# Cell_121_sheet_2.net
KiCad netlist of a schematic drawn in Altium Designer
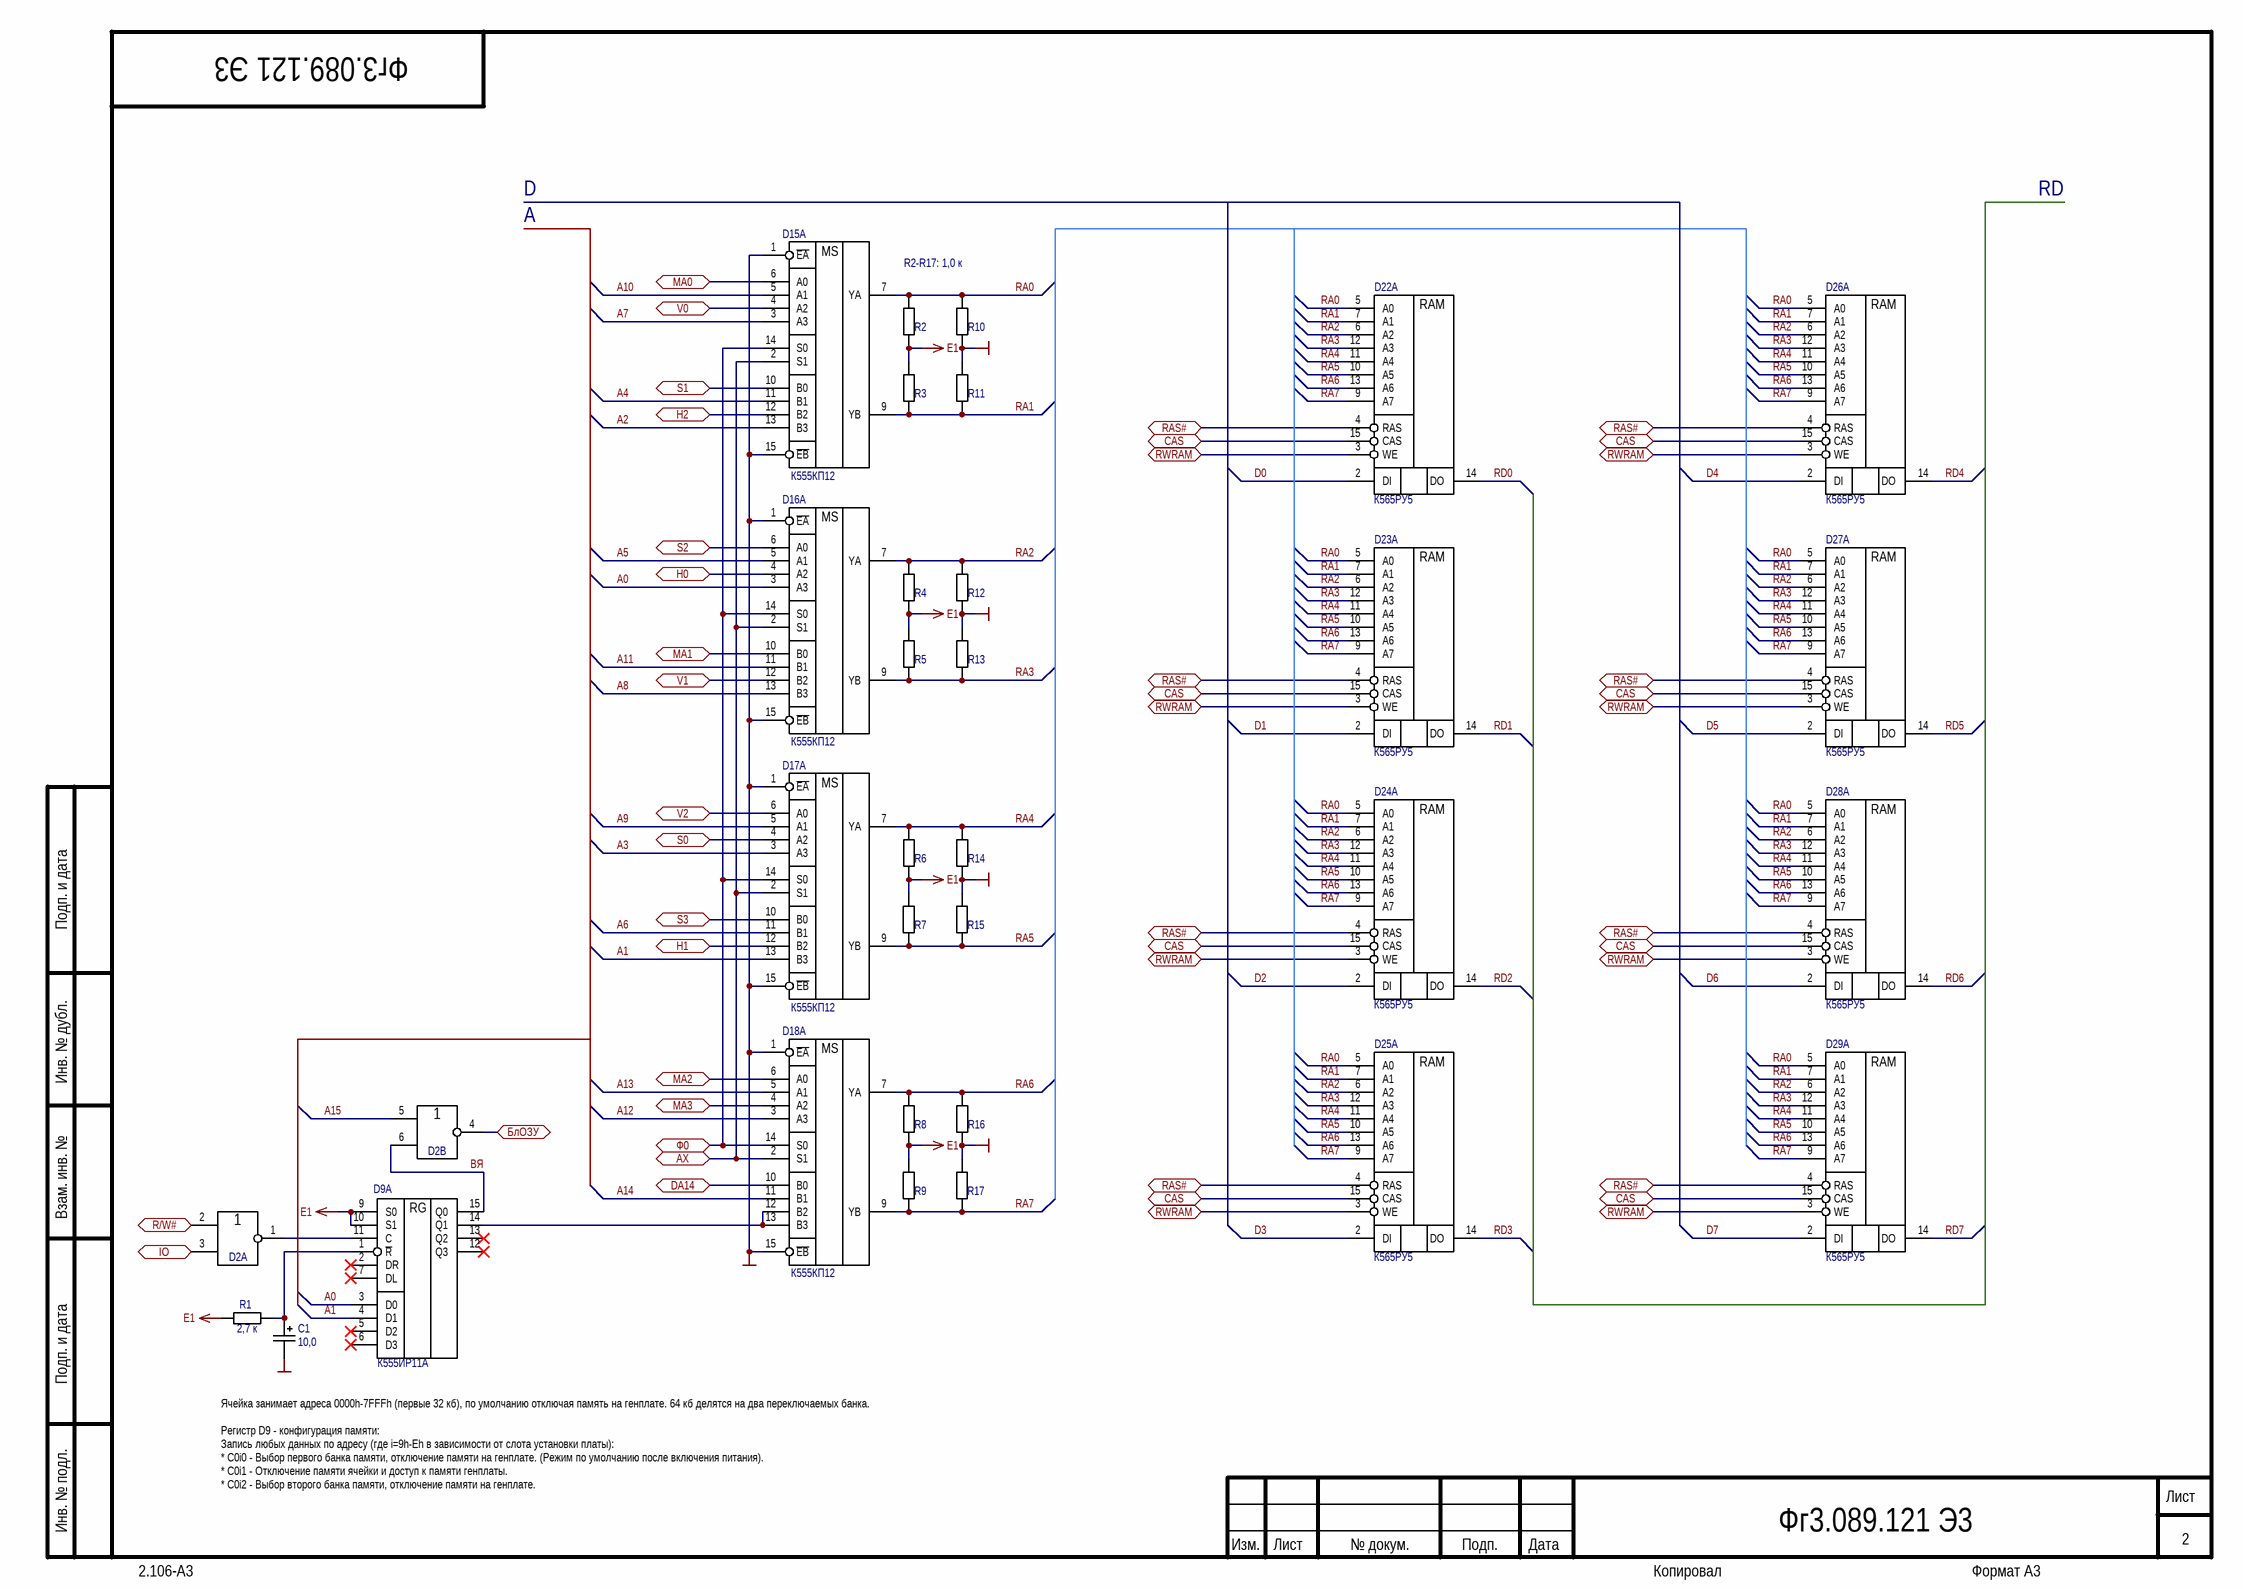
[diagram p0: Cell_121_sheet_2.SchDoc]

(export (version "E")
  (design (tool "Eeschema 10.0.6"))
  (components
    (comp (ref "C1")
      (value "10,0")
      (footprint "CP25")
      (description "К53-14")
      (libsource (lib "Agat") (part "К53-14"))
    )
    (comp (ref "D2")
      (value "К555ЛЕ1")
      (footprint "201.14")
      (fields (field (name "MANUFACTURERPARTNUMBER") "К555ЛА3"))
      (libsource (lib "Agat") (part "К555ЛЕ1"))
    )
    (comp (ref "D9")
      (value "К555ИР11А")
      (footprint "201.16")
      (fields (field (name "MANUFACTURERPARTNUMBER") "КР531ИЕ17"))
      (libsource (lib "Agat") (part "К555ИР11А"))
    )
    (comp (ref "D15")
      (value "К555КП12")
      (footprint "201.16")
      (fields (field (name "MANUFACTURERPARTNUMBER") "К155КП2"))
      (libsource (lib "Agat") (part "К555КП12"))
    )
    (comp (ref "D16")
      (value "К555КП12")
      (footprint "201.16")
      (fields (field (name "MANUFACTURERPARTNUMBER") "К155КП2"))
      (libsource (lib "Agat") (part "К555КП12"))
    )
    (comp (ref "D17")
      (value "К555КП12")
      (footprint "201.16")
      (fields (field (name "MANUFACTURERPARTNUMBER") "К155КП2"))
      (libsource (lib "Agat") (part "К555КП12"))
    )
    (comp (ref "D18")
      (value "К555КП12")
      (footprint "201.16")
      (fields (field (name "MANUFACTURERPARTNUMBER") "К155КП2"))
      (libsource (lib "Agat") (part "К555КП12"))
    )
    (comp (ref "D22") (value "К565РУ5") (footprint "201.16") (libsource (lib "Agat") (part "К565РУ5")))
    (comp (ref "D23") (value "К565РУ5") (footprint "201.16") (libsource (lib "Agat") (part "К565РУ5")))
    (comp (ref "D24") (value "К565РУ5") (footprint "201.16") (libsource (lib "Agat") (part "К565РУ5")))
    (comp (ref "D25") (value "К565РУ5") (footprint "201.16") (libsource (lib "Agat") (part "К565РУ5")))
    (comp (ref "D26") (value "К565РУ5") (footprint "201.16") (libsource (lib "Agat") (part "К565РУ5")))
    (comp (ref "D27") (value "К565РУ5") (footprint "201.16") (libsource (lib "Agat") (part "К565РУ5")))
    (comp (ref "D28") (value "К565РУ5") (footprint "201.16") (libsource (lib "Agat") (part "К565РУ5")))
    (comp (ref "D29") (value "К565РУ5") (footprint "201.16") (libsource (lib "Agat") (part "К565РУ5")))
    (comp (ref "R1")
      (value "2,7 к")
      (footprint "R10")
      (description "Резистор")
      (libsource (lib "") (part "С2-23_2"))
    )
    (comp (ref "R2")
      (value "1 к")
      (footprint "R10")
      (description "Резистор")
      (libsource (lib "Agat") (part "С2-23"))
    )
    (comp (ref "R3")
      (value "1 к")
      (footprint "R10")
      (description "Резистор")
      (libsource (lib "Agat") (part "С2-23"))
    )
    (comp (ref "R4")
      (value "1 к")
      (footprint "R10")
      (description "Резистор")
      (libsource (lib "Agat") (part "С2-23"))
    )
    (comp (ref "R5")
      (value "1 к")
      (footprint "R10")
      (description "Резистор")
      (libsource (lib "Agat") (part "С2-23"))
    )
    (comp (ref "R6")
      (value "1 к")
      (footprint "R10")
      (description "Резистор")
      (libsource (lib "Agat") (part "С2-23"))
    )
    (comp (ref "R7")
      (value "1 к")
      (footprint "R10")
      (description "Резистор")
      (libsource (lib "") (part "С2-23_1"))
    )
    (comp (ref "R8")
      (value "1 к")
      (footprint "R10")
      (description "Резистор")
      (libsource (lib "Agat") (part "С2-23"))
    )
    (comp (ref "R9")
      (value "1 к")
      (footprint "R10")
      (description "Резистор")
      (libsource (lib "") (part "С2-23_1"))
    )
    (comp (ref "R10")
      (value "1 к")
      (footprint "R10")
      (description "Резистор")
      (libsource (lib "Agat") (part "С2-23"))
    )
    (comp (ref "R11")
      (value "1 к")
      (footprint "R10")
      (description "Резистор")
      (libsource (lib "Agat") (part "С2-23"))
    )
    (comp (ref "R12")
      (value "1 к")
      (footprint "R10")
      (description "Резистор")
      (libsource (lib "Agat") (part "С2-23"))
    )
    (comp (ref "R13")
      (value "1 к")
      (footprint "R10")
      (description "Резистор")
      (libsource (lib "Agat") (part "С2-23"))
    )
    (comp (ref "R14")
      (value "1 к")
      (footprint "R10")
      (description "Резистор")
      (libsource (lib "Agat") (part "С2-23"))
    )
    (comp (ref "R15")
      (value "1 к")
      (footprint "R10")
      (description "Резистор")
      (libsource (lib "") (part "С2-23_1"))
    )
    (comp (ref "R16")
      (value "1 к")
      (footprint "R10")
      (description "Резистор")
      (libsource (lib "Agat") (part "С2-23"))
    )
    (comp (ref "R17")
      (value "1 к")
      (footprint "R10")
      (description "Резистор")
      (libsource (lib "") (part "С2-23_1"))
    )
  )
  (nets
    (net (code "1") (name "/A0") (class "Default")
      (node (ref "D16") (pin "3") (pinfunction "A3_3") (pintype "passive"))
      (node (ref "D9") (pin "3") (pinfunction "D0_3") (pintype "passive"))
    )
    (net (code "2") (name "/A1") (class "Default")
      (node (ref "D17") (pin "13") (pinfunction "B3_13") (pintype "passive"))
      (node (ref "D9") (pin "4") (pinfunction "D1_4") (pintype "passive"))
    )
    (net (code "3") (name "/A2") (class "Default")
      (node (ref "D15") (pin "13") (pinfunction "B3_13") (pintype "passive"))
    )
    (net (code "4") (name "/A3") (class "Default")
      (node (ref "D17") (pin "3") (pinfunction "A3_3") (pintype "passive"))
    )
    (net (code "5") (name "/A4") (class "Default")
      (node (ref "D15") (pin "11") (pinfunction "B1_11") (pintype "passive"))
    )
    (net (code "6") (name "/A5") (class "Default")
      (node (ref "D16") (pin "5") (pinfunction "A1_5") (pintype "passive"))
    )
    (net (code "7") (name "/A6") (class "Default")
      (node (ref "D17") (pin "11") (pinfunction "B1_11") (pintype "passive"))
    )
    (net (code "8") (name "/A7") (class "Default")
      (node (ref "D15") (pin "3") (pinfunction "A3_3") (pintype "passive"))
    )
    (net (code "9") (name "/A8") (class "Default")
      (node (ref "D16") (pin "13") (pinfunction "B3_13") (pintype "passive"))
    )
    (net (code "10") (name "/A9") (class "Default")
      (node (ref "D17") (pin "5") (pinfunction "A1_5") (pintype "passive"))
    )
    (net (code "11") (name "/A10") (class "Default")
      (node (ref "D15") (pin "5") (pinfunction "A1_5") (pintype "passive"))
    )
    (net (code "12") (name "/A11") (class "Default")
      (node (ref "D16") (pin "11") (pinfunction "B1_11") (pintype "passive"))
    )
    (net (code "13") (name "/A12") (class "Default")
      (node (ref "D18") (pin "3") (pinfunction "A3_3") (pintype "passive"))
    )
    (net (code "14") (name "/A13") (class "Default")
      (node (ref "D18") (pin "5") (pinfunction "A1_5") (pintype "passive"))
    )
    (net (code "15") (name "/A14") (class "Default")
      (node (ref "D18") (pin "11") (pinfunction "B1_11") (pintype "passive"))
    )
    (net (code "16") (name "/A15") (class "Default")
      (node (ref "D2") (pin "5") (pinfunction "A_5") (pintype "passive"))
    )
    (net (code "17") (name "/AX") (class "Default")
      (node (ref "D15") (pin "2") (pinfunction "S1_2") (pintype "passive"))
      (node (ref "D16") (pin "2") (pinfunction "S1_2") (pintype "passive"))
      (node (ref "D17") (pin "2") (pinfunction "S1_2") (pintype "passive"))
      (node (ref "D18") (pin "2") (pinfunction "S1_2") (pintype "passive"))
    )
    (net (code "18") (name "/CAS") (class "Default")
      (node (ref "D22") (pin "15") (pinfunction "CAS_15") (pintype "passive"))
      (node (ref "D23") (pin "15") (pinfunction "CAS_15") (pintype "passive"))
      (node (ref "D24") (pin "15") (pinfunction "CAS_15") (pintype "passive"))
      (node (ref "D25") (pin "15") (pinfunction "CAS_15") (pintype "passive"))
      (node (ref "D26") (pin "15") (pinfunction "CAS_15") (pintype "passive"))
      (node (ref "D27") (pin "15") (pinfunction "CAS_15") (pintype "passive"))
      (node (ref "D28") (pin "15") (pinfunction "CAS_15") (pintype "passive"))
      (node (ref "D29") (pin "15") (pinfunction "CAS_15") (pintype "passive"))
    )
    (net (code "19") (name "/D0") (class "Default")
      (node (ref "D22") (pin "2") (pinfunction "DI_2") (pintype "passive"))
    )
    (net (code "20") (name "/D1") (class "Default")
      (node (ref "D23") (pin "2") (pinfunction "DI_2") (pintype "passive"))
    )
    (net (code "21") (name "/D2") (class "Default")
      (node (ref "D24") (pin "2") (pinfunction "DI_2") (pintype "passive"))
    )
    (net (code "22") (name "/D3") (class "Default")
      (node (ref "D25") (pin "2") (pinfunction "DI_2") (pintype "passive"))
    )
    (net (code "23") (name "/D4") (class "Default")
      (node (ref "D26") (pin "2") (pinfunction "DI_2") (pintype "passive"))
    )
    (net (code "24") (name "/D5") (class "Default")
      (node (ref "D27") (pin "2") (pinfunction "DI_2") (pintype "passive"))
    )
    (net (code "25") (name "/D6") (class "Default")
      (node (ref "D28") (pin "2") (pinfunction "DI_2") (pintype "passive"))
    )
    (net (code "26") (name "/D7") (class "Default")
      (node (ref "D29") (pin "2") (pinfunction "DI_2") (pintype "passive"))
    )
    (net (code "27") (name "/DA14") (class "Default")
      (node (ref "D18") (pin "10") (pinfunction "B0_10") (pintype "passive"))
    )
    (net (code "28") (name "/H0") (class "Default")
      (node (ref "D16") (pin "4") (pinfunction "A2_4") (pintype "passive"))
    )
    (net (code "29") (name "/H1") (class "Default")
      (node (ref "D17") (pin "12") (pinfunction "B2_12") (pintype "passive"))
    )
    (net (code "30") (name "/H2") (class "Default")
      (node (ref "D15") (pin "12") (pinfunction "B2_12") (pintype "passive"))
    )
    (net (code "31") (name "/IO") (class "Default")
      (node (ref "D2") (pin "3") (pinfunction "B_3") (pintype "passive"))
    )
    (net (code "32") (name "/MA0") (class "Default")
      (node (ref "D15") (pin "6") (pinfunction "A0_6") (pintype "passive"))
    )
    (net (code "33") (name "/MA1") (class "Default")
      (node (ref "D16") (pin "10") (pinfunction "B0_10") (pintype "passive"))
    )
    (net (code "34") (name "/MA2") (class "Default")
      (node (ref "D18") (pin "6") (pinfunction "A0_6") (pintype "passive"))
    )
    (net (code "35") (name "/MA3") (class "Default")
      (node (ref "D18") (pin "4") (pinfunction "A2_4") (pintype "passive"))
    )
    (net (code "36") (name "/RA0") (class "Default")
      (node (ref "D15") (pin "7") (pinfunction "YA_7") (pintype "passive"))
      (node (ref "D22") (pin "5") (pinfunction "A0_5") (pintype "passive"))
      (node (ref "D23") (pin "5") (pinfunction "A0_5") (pintype "passive"))
      (node (ref "D24") (pin "5") (pinfunction "A0_5") (pintype "passive"))
      (node (ref "D25") (pin "5") (pinfunction "A0_5") (pintype "passive"))
      (node (ref "D26") (pin "5") (pinfunction "A0_5") (pintype "passive"))
      (node (ref "D27") (pin "5") (pinfunction "A0_5") (pintype "passive"))
      (node (ref "D28") (pin "5") (pinfunction "A0_5") (pintype "passive"))
      (node (ref "D29") (pin "5") (pinfunction "A0_5") (pintype "passive"))
      (node (ref "R10") (pin "1") (pinfunction "1_1") (pintype "passive"))
      (node (ref "R2") (pin "1") (pinfunction "1_1") (pintype "passive"))
    )
    (net (code "37") (name "/RA1") (class "Default")
      (node (ref "D15") (pin "9") (pinfunction "YB_9") (pintype "passive"))
      (node (ref "D22") (pin "7") (pinfunction "A1_7") (pintype "passive"))
      (node (ref "D23") (pin "7") (pinfunction "A1_7") (pintype "passive"))
      (node (ref "D24") (pin "7") (pinfunction "A1_7") (pintype "passive"))
      (node (ref "D25") (pin "7") (pinfunction "A1_7") (pintype "passive"))
      (node (ref "D26") (pin "7") (pinfunction "A1_7") (pintype "passive"))
      (node (ref "D27") (pin "7") (pinfunction "A1_7") (pintype "passive"))
      (node (ref "D28") (pin "7") (pinfunction "A1_7") (pintype "passive"))
      (node (ref "D29") (pin "7") (pinfunction "A1_7") (pintype "passive"))
      (node (ref "R11") (pin "2") (pinfunction "2_2") (pintype "passive"))
      (node (ref "R3") (pin "2") (pinfunction "2_2") (pintype "passive"))
    )
    (net (code "38") (name "/RA2") (class "Default")
      (node (ref "D16") (pin "7") (pinfunction "YA_7") (pintype "passive"))
      (node (ref "D22") (pin "6") (pinfunction "A2_6") (pintype "passive"))
      (node (ref "D23") (pin "6") (pinfunction "A2_6") (pintype "passive"))
      (node (ref "D24") (pin "6") (pinfunction "A2_6") (pintype "passive"))
      (node (ref "D25") (pin "6") (pinfunction "A2_6") (pintype "passive"))
      (node (ref "D26") (pin "6") (pinfunction "A2_6") (pintype "passive"))
      (node (ref "D27") (pin "6") (pinfunction "A2_6") (pintype "passive"))
      (node (ref "D28") (pin "6") (pinfunction "A2_6") (pintype "passive"))
      (node (ref "D29") (pin "6") (pinfunction "A2_6") (pintype "passive"))
      (node (ref "R12") (pin "1") (pinfunction "1_1") (pintype "passive"))
      (node (ref "R4") (pin "1") (pinfunction "1_1") (pintype "passive"))
    )
    (net (code "39") (name "/RA3") (class "Default")
      (node (ref "D16") (pin "9") (pinfunction "YB_9") (pintype "passive"))
      (node (ref "D22") (pin "12") (pinfunction "A3_12") (pintype "passive"))
      (node (ref "D23") (pin "12") (pinfunction "A3_12") (pintype "passive"))
      (node (ref "D24") (pin "12") (pinfunction "A3_12") (pintype "passive"))
      (node (ref "D25") (pin "12") (pinfunction "A3_12") (pintype "passive"))
      (node (ref "D26") (pin "12") (pinfunction "A3_12") (pintype "passive"))
      (node (ref "D27") (pin "12") (pinfunction "A3_12") (pintype "passive"))
      (node (ref "D28") (pin "12") (pinfunction "A3_12") (pintype "passive"))
      (node (ref "D29") (pin "12") (pinfunction "A3_12") (pintype "passive"))
      (node (ref "R13") (pin "2") (pinfunction "2_2") (pintype "passive"))
      (node (ref "R5") (pin "2") (pinfunction "2_2") (pintype "passive"))
    )
    (net (code "40") (name "/RA4") (class "Default")
      (node (ref "D17") (pin "7") (pinfunction "YA_7") (pintype "passive"))
      (node (ref "D22") (pin "11") (pinfunction "A4_11") (pintype "passive"))
      (node (ref "D23") (pin "11") (pinfunction "A4_11") (pintype "passive"))
      (node (ref "D24") (pin "11") (pinfunction "A4_11") (pintype "passive"))
      (node (ref "D25") (pin "11") (pinfunction "A4_11") (pintype "passive"))
      (node (ref "D26") (pin "11") (pinfunction "A4_11") (pintype "passive"))
      (node (ref "D27") (pin "11") (pinfunction "A4_11") (pintype "passive"))
      (node (ref "D28") (pin "11") (pinfunction "A4_11") (pintype "passive"))
      (node (ref "D29") (pin "11") (pinfunction "A4_11") (pintype "passive"))
      (node (ref "R14") (pin "1") (pinfunction "1_1") (pintype "passive"))
      (node (ref "R6") (pin "1") (pinfunction "1_1") (pintype "passive"))
    )
    (net (code "41") (name "/RA5") (class "Default")
      (node (ref "D17") (pin "9") (pinfunction "YB_9") (pintype "passive"))
      (node (ref "D22") (pin "10") (pinfunction "A5_10") (pintype "passive"))
      (node (ref "D23") (pin "10") (pinfunction "A5_10") (pintype "passive"))
      (node (ref "D24") (pin "10") (pinfunction "A5_10") (pintype "passive"))
      (node (ref "D25") (pin "10") (pinfunction "A5_10") (pintype "passive"))
      (node (ref "D26") (pin "10") (pinfunction "A5_10") (pintype "passive"))
      (node (ref "D27") (pin "10") (pinfunction "A5_10") (pintype "passive"))
      (node (ref "D28") (pin "10") (pinfunction "A5_10") (pintype "passive"))
      (node (ref "D29") (pin "10") (pinfunction "A5_10") (pintype "passive"))
      (node (ref "R15") (pin "1") (pinfunction "1_1") (pintype "passive"))
      (node (ref "R7") (pin "1") (pinfunction "1_1") (pintype "passive"))
    )
    (net (code "42") (name "/RA6") (class "Default")
      (node (ref "D18") (pin "7") (pinfunction "YA_7") (pintype "passive"))
      (node (ref "D22") (pin "13") (pinfunction "A6_13") (pintype "passive"))
      (node (ref "D23") (pin "13") (pinfunction "A6_13") (pintype "passive"))
      (node (ref "D24") (pin "13") (pinfunction "A6_13") (pintype "passive"))
      (node (ref "D25") (pin "13") (pinfunction "A6_13") (pintype "passive"))
      (node (ref "D26") (pin "13") (pinfunction "A6_13") (pintype "passive"))
      (node (ref "D27") (pin "13") (pinfunction "A6_13") (pintype "passive"))
      (node (ref "D28") (pin "13") (pinfunction "A6_13") (pintype "passive"))
      (node (ref "D29") (pin "13") (pinfunction "A6_13") (pintype "passive"))
      (node (ref "R16") (pin "1") (pinfunction "1_1") (pintype "passive"))
      (node (ref "R8") (pin "1") (pinfunction "1_1") (pintype "passive"))
    )
    (net (code "43") (name "/RA7") (class "Default")
      (node (ref "D18") (pin "9") (pinfunction "YB_9") (pintype "passive"))
      (node (ref "D22") (pin "9") (pinfunction "A7_9") (pintype "passive"))
      (node (ref "D23") (pin "9") (pinfunction "A7_9") (pintype "passive"))
      (node (ref "D24") (pin "9") (pinfunction "A7_9") (pintype "passive"))
      (node (ref "D25") (pin "9") (pinfunction "A7_9") (pintype "passive"))
      (node (ref "D26") (pin "9") (pinfunction "A7_9") (pintype "passive"))
      (node (ref "D27") (pin "9") (pinfunction "A7_9") (pintype "passive"))
      (node (ref "D28") (pin "9") (pinfunction "A7_9") (pintype "passive"))
      (node (ref "D29") (pin "9") (pinfunction "A7_9") (pintype "passive"))
      (node (ref "R17") (pin "1") (pinfunction "1_1") (pintype "passive"))
      (node (ref "R9") (pin "1") (pinfunction "1_1") (pintype "passive"))
    )
    (net (code "44") (name "/RAS#") (class "Default")
      (node (ref "D22") (pin "4") (pinfunction "RAS_4") (pintype "passive"))
      (node (ref "D23") (pin "4") (pinfunction "RAS_4") (pintype "passive"))
      (node (ref "D24") (pin "4") (pinfunction "RAS_4") (pintype "passive"))
      (node (ref "D25") (pin "4") (pinfunction "RAS_4") (pintype "passive"))
      (node (ref "D26") (pin "4") (pinfunction "RAS_4") (pintype "passive"))
      (node (ref "D27") (pin "4") (pinfunction "RAS_4") (pintype "passive"))
      (node (ref "D28") (pin "4") (pinfunction "RAS_4") (pintype "passive"))
      (node (ref "D29") (pin "4") (pinfunction "RAS_4") (pintype "passive"))
    )
    (net (code "45") (name "/RD0") (class "Default")
      (node (ref "D22") (pin "14") (pinfunction "DO_14") (pintype "passive"))
    )
    (net (code "46") (name "/RD1") (class "Default")
      (node (ref "D23") (pin "14") (pinfunction "DO_14") (pintype "passive"))
    )
    (net (code "47") (name "/RD2") (class "Default")
      (node (ref "D24") (pin "14") (pinfunction "DO_14") (pintype "passive"))
    )
    (net (code "48") (name "/RD3") (class "Default")
      (node (ref "D25") (pin "14") (pinfunction "DO_14") (pintype "passive"))
    )
    (net (code "49") (name "/RD4") (class "Default")
      (node (ref "D26") (pin "14") (pinfunction "DO_14") (pintype "passive"))
    )
    (net (code "50") (name "/RD5") (class "Default")
      (node (ref "D27") (pin "14") (pinfunction "DO_14") (pintype "passive"))
    )
    (net (code "51") (name "/RD6") (class "Default")
      (node (ref "D28") (pin "14") (pinfunction "DO_14") (pintype "passive"))
    )
    (net (code "52") (name "/RD7") (class "Default")
      (node (ref "D29") (pin "14") (pinfunction "DO_14") (pintype "passive"))
    )
    (net (code "53") (name "/RWRAM") (class "Default")
      (node (ref "D22") (pin "3") (pinfunction "WE_3") (pintype "passive"))
      (node (ref "D23") (pin "3") (pinfunction "WE_3") (pintype "passive"))
      (node (ref "D24") (pin "3") (pinfunction "WE_3") (pintype "passive"))
      (node (ref "D25") (pin "3") (pinfunction "WE_3") (pintype "passive"))
      (node (ref "D26") (pin "3") (pinfunction "WE_3") (pintype "passive"))
      (node (ref "D27") (pin "3") (pinfunction "WE_3") (pintype "passive"))
      (node (ref "D28") (pin "3") (pinfunction "WE_3") (pintype "passive"))
      (node (ref "D29") (pin "3") (pinfunction "WE_3") (pintype "passive"))
    )
    (net (code "54") (name "/R{slash}W#") (class "Default")
      (node (ref "D2") (pin "2") (pinfunction "A_2") (pintype "passive"))
    )
    (net (code "55") (name "/S0") (class "Default")
      (node (ref "D17") (pin "4") (pinfunction "A2_4") (pintype "passive"))
    )
    (net (code "56") (name "/S1") (class "Default")
      (node (ref "D15") (pin "10") (pinfunction "B0_10") (pintype "passive"))
    )
    (net (code "57") (name "/S2") (class "Default")
      (node (ref "D16") (pin "6") (pinfunction "A0_6") (pintype "passive"))
    )
    (net (code "58") (name "/S3") (class "Default")
      (node (ref "D17") (pin "10") (pinfunction "B0_10") (pintype "passive"))
    )
    (net (code "59") (name "/V0") (class "Default")
      (node (ref "D15") (pin "4") (pinfunction "A2_4") (pintype "passive"))
    )
    (net (code "60") (name "/V1") (class "Default")
      (node (ref "D16") (pin "12") (pinfunction "B2_12") (pintype "passive"))
    )
    (net (code "61") (name "/V2") (class "Default")
      (node (ref "D17") (pin "6") (pinfunction "A0_6") (pintype "passive"))
    )
    (net (code "62") (name "/БлОЗУ") (class "Default")
      (node (ref "D2") (pin "4") (pinfunction "~{O}_4") (pintype "passive"))
    )
    (net (code "63") (name "/ВЯ") (class "Default")
      (node (ref "D2") (pin "6") (pinfunction "B_6") (pintype "passive"))
      (node (ref "D9") (pin "15") (pinfunction "Q0_15") (pintype "passive"))
    )
    (net (code "64") (name "/Ф0") (class "Default")
      (node (ref "D15") (pin "14") (pinfunction "S0_14") (pintype "passive"))
      (node (ref "D16") (pin "14") (pinfunction "S0_14") (pintype "passive"))
      (node (ref "D17") (pin "14") (pinfunction "S0_14") (pintype "passive"))
      (node (ref "D18") (pin "14") (pinfunction "S0_14") (pintype "passive"))
    )
    (net (code "65") (name "E1") (class "Default")
      (node (ref "D9") (pin "10") (pinfunction "S1_10") (pintype "passive"))
      (node (ref "D9") (pin "9") (pinfunction "S0_9") (pintype "passive"))
      (node (ref "R1") (pin "2") (pinfunction "2_2") (pintype "passive"))
      (node (ref "R2") (pin "2") (pinfunction "2_2") (pintype "passive"))
      (node (ref "R3") (pin "1") (pinfunction "1_1") (pintype "passive"))
      (node (ref "R4") (pin "2") (pinfunction "2_2") (pintype "passive"))
      (node (ref "R5") (pin "1") (pinfunction "1_1") (pintype "passive"))
      (node (ref "R6") (pin "2") (pinfunction "2_2") (pintype "passive"))
      (node (ref "R7") (pin "2") (pinfunction "2_2") (pintype "passive"))
      (node (ref "R8") (pin "2") (pinfunction "2_2") (pintype "passive"))
      (node (ref "R9") (pin "2") (pinfunction "2_2") (pintype "passive"))
    )
    (net (code "66") (name "GND") (class "Default")
      (node (ref "C1") (pin "2") (pintype "passive"))
      (node (ref "D15") (pin "1") (pinfunction "~{EA}_1") (pintype "passive"))
      (node (ref "D15") (pin "15") (pinfunction "~{EB}_15") (pintype "passive"))
      (node (ref "D16") (pin "1") (pinfunction "~{EA}_1") (pintype "passive"))
      (node (ref "D16") (pin "15") (pinfunction "~{EB}_15") (pintype "passive"))
      (node (ref "D17") (pin "1") (pinfunction "~{EA}_1") (pintype "passive"))
      (node (ref "D17") (pin "15") (pinfunction "~{EB}_15") (pintype "passive"))
      (node (ref "D18") (pin "1") (pinfunction "~{EA}_1") (pintype "passive"))
      (node (ref "D18") (pin "15") (pinfunction "~{EB}_15") (pintype "passive"))
      (node (ref "R10") (pin "2") (pinfunction "2_2") (pintype "passive"))
      (node (ref "R11") (pin "1") (pinfunction "1_1") (pintype "passive"))
      (node (ref "R12") (pin "2") (pinfunction "2_2") (pintype "passive"))
      (node (ref "R13") (pin "1") (pinfunction "1_1") (pintype "passive"))
      (node (ref "R14") (pin "2") (pinfunction "2_2") (pintype "passive"))
      (node (ref "R15") (pin "2") (pinfunction "2_2") (pintype "passive"))
      (node (ref "R16") (pin "2") (pinfunction "2_2") (pintype "passive"))
      (node (ref "R17") (pin "2") (pinfunction "2_2") (pintype "passive"))
    )
    (net (code "67") (name "Net-(D2A-~{O})") (class "Default")
      (node (ref "D2") (pin "1") (pinfunction "~{O}_1") (pintype "passive"))
      (node (ref "D9") (pin "11") (pinfunction "C_11") (pintype "passive"))
    )
    (net (code "68") (name "Net-(D9A-~{R})") (class "Default")
      (node (ref "C1") (pin "1") (pintype "passive"))
      (node (ref "D9") (pin "1") (pinfunction "~{R}_1") (pintype "passive"))
      (node (ref "R1") (pin "1") (pinfunction "1_1") (pintype "passive"))
    )
    (net (code "69") (name "Net-(D18A-B2)") (class "Default")
      (node (ref "D18") (pin "12") (pinfunction "B2_12") (pintype "passive"))
      (node (ref "D18") (pin "13") (pinfunction "B3_13") (pintype "passive"))
      (node (ref "D9") (pin "14") (pinfunction "Q1_14") (pintype "passive"))
    )
    (net (code "70") (name "unconnected-(D9A-D2-Pad5)") (class "Default")
      (node (ref "D9") (pin "5") (pinfunction "D2_5") (pintype "passive+no_connect"))
    )
    (net (code "71") (name "unconnected-(D9A-D3-Pad6)") (class "Default")
      (node (ref "D9") (pin "6") (pinfunction "D3_6") (pintype "passive+no_connect"))
    )
    (net (code "72") (name "unconnected-(D9A-DL-Pad7)") (class "Default")
      (node (ref "D9") (pin "7") (pinfunction "DL_7") (pintype "passive+no_connect"))
    )
    (net (code "73") (name "unconnected-(D9A-DR-Pad2)") (class "Default")
      (node (ref "D9") (pin "2") (pinfunction "DR_2") (pintype "passive+no_connect"))
    )
    (net (code "74") (name "unconnected-(D9A-Q2-Pad13)") (class "Default")
      (node (ref "D9") (pin "13") (pinfunction "Q2_13") (pintype "passive+no_connect"))
    )
    (net (code "75") (name "unconnected-(D9A-Q3-Pad12)") (class "Default")
      (node (ref "D9") (pin "12") (pinfunction "Q3_12") (pintype "passive+no_connect"))
    )
  )
)
